# wearable.net
KiCad netlist of a schematic drawn in EAGLE
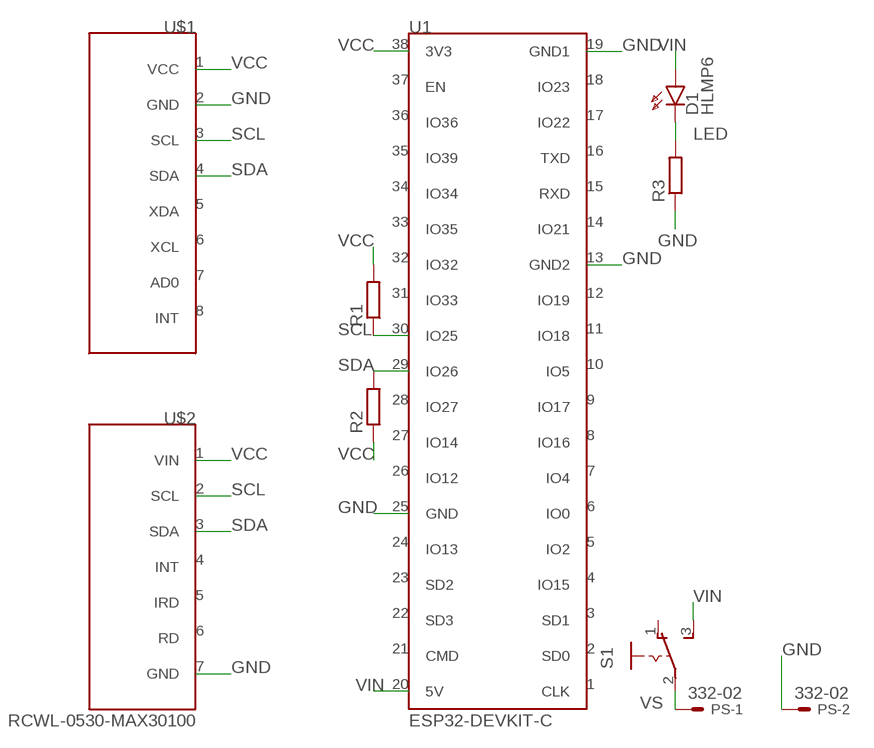
[diagram p0: schematic, sheet 1]

(export (version "E")
  (design (tool "Eeschema 10.0.6"))
  (components
    (comp (ref "D1")
      (value "HLMP6")
      (footprint "eagle-import:HLMP6")
      (fields (field (name "MF") "AGILENT TECHNOLOGIES") (field (name "MPN") "HLMP-6500"))
      (libsource (lib "eagle-import") (part "HLMP6"))
    )
    (comp (ref "PS")
      (value "332-02")
      (footprint "eagle-import:332-02")
      (libsource (lib "eagle-import") (part "332-02"))
    )
    (comp (ref "R1")
      (value "R-EU_0207/10")
      (footprint "eagle-import:0207_10")
      (libsource (lib "eagle-import") (part "R-EU_0207/10"))
    )
    (comp (ref "R2")
      (value "R-EU_0207/10")
      (footprint "eagle-import:0207_10")
      (libsource (lib "eagle-import") (part "R-EU_0207/10"))
    )
    (comp (ref "R3")
      (value "R-EU_0207/10")
      (footprint "eagle-import:0207_10")
      (libsource (lib "eagle-import") (part "R-EU_0207/10"))
    )
    (comp (ref "S1")
      (value "255SB")
      (footprint "eagle-import:255SB")
      (libsource (lib "eagle-import") (part "255SB"))
    )
    (comp (ref "U$1")
      (value "GY-521-MPU-6050")
      (footprint "eagle-import:GY-521")
      (libsource (lib "eagle-import") (part "GY-521-MPU-6050"))
    )
    (comp (ref "U$2")
      (value "RCWL-0530-MAX30100")
      (footprint "eagle-import:RCWL-0530")
      (libsource (lib "eagle-import") (part "RCWL-0530-MAX30100"))
    )
    (comp (ref "U1")
      (value "ESP32-DEVKIT-C")
      (footprint "eagle-import:ESP32")
      (libsource (lib "eagle-import") (part "ESP32-DEVKIT-C"))
    )
  )
  (nets
    (net (code "1") (name "/GND") (class "Default")
      (node (ref "PS") (pin "2") (pinfunction "S_2") (pintype "passive"))
      (node (ref "R3") (pin "1") (pinfunction "1_1") (pintype "passive"))
      (node (ref "U$1") (pin "2") (pinfunction "GND_2") (pintype "bidirectional"))
      (node (ref "U$2") (pin "7") (pinfunction "GND_7") (pintype "bidirectional"))
      (node (ref "U1") (pin "13") (pinfunction "GND2_13") (pintype "power_in"))
      (node (ref "U1") (pin "19") (pinfunction "GND1_19") (pintype "power_in"))
      (node (ref "U1") (pin "25") (pinfunction "GND_25") (pintype "power_in"))
    )
    (net (code "2") (name "/LED") (class "Default")
      (node (ref "D1") (pin "K") (pinfunction "K_K") (pintype "passive"))
      (node (ref "R3") (pin "2") (pinfunction "2_2") (pintype "passive"))
    )
    (net (code "3") (name "/SCL") (class "Default")
      (node (ref "R1") (pin "1") (pinfunction "1_1") (pintype "passive"))
      (node (ref "U$1") (pin "3") (pinfunction "SCL_3") (pintype "bidirectional"))
      (node (ref "U$2") (pin "2") (pinfunction "SCL_2") (pintype "bidirectional"))
      (node (ref "U1") (pin "30") (pinfunction "IO25_30") (pintype "bidirectional"))
    )
    (net (code "4") (name "/SDA") (class "Default")
      (node (ref "R2") (pin "2") (pinfunction "2_2") (pintype "passive"))
      (node (ref "U$1") (pin "4") (pinfunction "SDA_4") (pintype "bidirectional"))
      (node (ref "U$2") (pin "3") (pinfunction "SDA_3") (pintype "bidirectional"))
      (node (ref "U1") (pin "29") (pinfunction "IO26_29") (pintype "bidirectional"))
    )
    (net (code "5") (name "/VCC") (class "Default")
      (node (ref "R1") (pin "2") (pinfunction "2_2") (pintype "passive"))
      (node (ref "R2") (pin "1") (pinfunction "1_1") (pintype "passive"))
      (node (ref "U$1") (pin "1") (pinfunction "VCC_1") (pintype "bidirectional"))
      (node (ref "U$2") (pin "1") (pinfunction "VIN_1") (pintype "bidirectional"))
      (node (ref "U1") (pin "38") (pinfunction "3V3_38") (pintype "power_in"))
    )
    (net (code "6") (name "/VIN") (class "Default")
      (node (ref "D1") (pin "A") (pinfunction "A_A") (pintype "passive"))
      (node (ref "S1") (pin "3") (pinfunction "S_3") (pintype "passive"))
      (node (ref "U1") (pin "20") (pinfunction "5V_20") (pintype "power_in"))
    )
    (net (code "7") (name "/VS") (class "Default")
      (node (ref "PS") (pin "1") (pinfunction "S_1") (pintype "passive"))
      (node (ref "S1") (pin "2") (pinfunction "P_2") (pintype "passive"))
    )
    (net (code "8") (name "unconnected-(S1-O-Pad1)") (class "Default")
      (node (ref "S1") (pin "1") (pinfunction "O_1") (pintype "passive"))
    )
    (net (code "9") (name "unconnected-(U$1-AD0-Pad7)") (class "Default")
      (node (ref "U$1") (pin "7") (pinfunction "AD0_7") (pintype "bidirectional"))
    )
    (net (code "10") (name "unconnected-(U$1-INT-Pad8)") (class "Default")
      (node (ref "U$1") (pin "8") (pinfunction "INT_8") (pintype "bidirectional"))
    )
    (net (code "11") (name "unconnected-(U$1-XCL-Pad6)") (class "Default")
      (node (ref "U$1") (pin "6") (pinfunction "XCL_6") (pintype "bidirectional"))
    )
    (net (code "12") (name "unconnected-(U$1-XDA-Pad5)") (class "Default")
      (node (ref "U$1") (pin "5") (pinfunction "XDA_5") (pintype "bidirectional"))
    )
    (net (code "13") (name "unconnected-(U$2-INT-Pad4)") (class "Default")
      (node (ref "U$2") (pin "4") (pinfunction "INT_4") (pintype "bidirectional"))
    )
    (net (code "14") (name "unconnected-(U$2-IRD-Pad5)") (class "Default")
      (node (ref "U$2") (pin "5") (pinfunction "IRD_5") (pintype "bidirectional"))
    )
    (net (code "15") (name "unconnected-(U$2-RD-Pad6)") (class "Default")
      (node (ref "U$2") (pin "6") (pinfunction "RD_6") (pintype "bidirectional"))
    )
    (net (code "16") (name "unconnected-(U1-CLK-Pad1)") (class "Default")
      (node (ref "U1") (pin "1") (pinfunction "CLK_1") (pintype "no_connect"))
    )
    (net (code "17") (name "unconnected-(U1-CMD-Pad21)") (class "Default")
      (node (ref "U1") (pin "21") (pinfunction "CMD_21") (pintype "no_connect"))
    )
    (net (code "18") (name "unconnected-(U1-EN-Pad37)") (class "Default")
      (node (ref "U1") (pin "37") (pinfunction "EN_37") (pintype "bidirectional"))
    )
    (net (code "19") (name "unconnected-(U1-IO0-Pad6)") (class "Default")
      (node (ref "U1") (pin "6") (pinfunction "IO0_6") (pintype "output"))
    )
    (net (code "20") (name "unconnected-(U1-IO2-Pad5)") (class "Default")
      (node (ref "U1") (pin "5") (pinfunction "IO2_5") (pintype "output"))
    )
    (net (code "21") (name "unconnected-(U1-IO4-Pad7)") (class "Default")
      (node (ref "U1") (pin "7") (pinfunction "IO4_7") (pintype "output"))
    )
    (net (code "22") (name "unconnected-(U1-IO5-Pad10)") (class "Default")
      (node (ref "U1") (pin "10") (pinfunction "IO5_10") (pintype "output"))
    )
    (net (code "23") (name "unconnected-(U1-IO12-Pad26)") (class "Default")
      (node (ref "U1") (pin "26") (pinfunction "IO12_26") (pintype "output"))
    )
    (net (code "24") (name "unconnected-(U1-IO13-Pad24)") (class "Default")
      (node (ref "U1") (pin "24") (pinfunction "IO13_24") (pintype "bidirectional"))
    )
    (net (code "25") (name "unconnected-(U1-IO14-Pad27)") (class "Default")
      (node (ref "U1") (pin "27") (pinfunction "IO14_27") (pintype "bidirectional"))
    )
    (net (code "26") (name "unconnected-(U1-IO15-Pad4)") (class "Default")
      (node (ref "U1") (pin "4") (pinfunction "IO15_4") (pintype "output"))
    )
    (net (code "27") (name "unconnected-(U1-IO16-Pad8)") (class "Default")
      (node (ref "U1") (pin "8") (pinfunction "IO16_8") (pintype "bidirectional"))
    )
    (net (code "28") (name "unconnected-(U1-IO17-Pad9)") (class "Default")
      (node (ref "U1") (pin "9") (pinfunction "IO17_9") (pintype "bidirectional"))
    )
    (net (code "29") (name "unconnected-(U1-IO18-Pad11)") (class "Default")
      (node (ref "U1") (pin "11") (pinfunction "IO18_11") (pintype "bidirectional"))
    )
    (net (code "30") (name "unconnected-(U1-IO19-Pad12)") (class "Default")
      (node (ref "U1") (pin "12") (pinfunction "IO19_12") (pintype "bidirectional"))
    )
    (net (code "31") (name "unconnected-(U1-IO21-Pad14)") (class "Default")
      (node (ref "U1") (pin "14") (pinfunction "IO21_14") (pintype "bidirectional"))
    )
    (net (code "32") (name "unconnected-(U1-IO22-Pad17)") (class "Default")
      (node (ref "U1") (pin "17") (pinfunction "IO22_17") (pintype "bidirectional"))
    )
    (net (code "33") (name "unconnected-(U1-IO23-Pad18)") (class "Default")
      (node (ref "U1") (pin "18") (pinfunction "IO23_18") (pintype "bidirectional"))
    )
    (net (code "34") (name "unconnected-(U1-IO27-Pad28)") (class "Default")
      (node (ref "U1") (pin "28") (pinfunction "IO27_28") (pintype "bidirectional"))
    )
    (net (code "35") (name "unconnected-(U1-IO32-Pad32)") (class "Default")
      (node (ref "U1") (pin "32") (pinfunction "IO32_32") (pintype "bidirectional"))
    )
    (net (code "36") (name "unconnected-(U1-IO33-Pad31)") (class "Default")
      (node (ref "U1") (pin "31") (pinfunction "IO33_31") (pintype "bidirectional"))
    )
    (net (code "37") (name "unconnected-(U1-IO34-Pad34)") (class "Default")
      (node (ref "U1") (pin "34") (pinfunction "IO34_34") (pintype "input"))
    )
    (net (code "38") (name "unconnected-(U1-IO35-Pad33)") (class "Default")
      (node (ref "U1") (pin "33") (pinfunction "IO35_33") (pintype "input"))
    )
    (net (code "39") (name "unconnected-(U1-IO36-Pad36)") (class "Default")
      (node (ref "U1") (pin "36") (pinfunction "IO36_36") (pintype "input"))
    )
    (net (code "40") (name "unconnected-(U1-IO39-Pad35)") (class "Default")
      (node (ref "U1") (pin "35") (pinfunction "IO39_35") (pintype "input"))
    )
    (net (code "41") (name "unconnected-(U1-RXD-Pad15)") (class "Default")
      (node (ref "U1") (pin "15") (pinfunction "RXD_15") (pintype "no_connect"))
    )
    (net (code "42") (name "unconnected-(U1-SD0-Pad2)") (class "Default")
      (node (ref "U1") (pin "2") (pinfunction "SD0_2") (pintype "no_connect"))
    )
    (net (code "43") (name "unconnected-(U1-SD1-Pad3)") (class "Default")
      (node (ref "U1") (pin "3") (pinfunction "SD1_3") (pintype "no_connect"))
    )
    (net (code "44") (name "unconnected-(U1-SD2-Pad23)") (class "Default")
      (node (ref "U1") (pin "23") (pinfunction "SD2_23") (pintype "no_connect"))
    )
    (net (code "45") (name "unconnected-(U1-SD3-Pad22)") (class "Default")
      (node (ref "U1") (pin "22") (pinfunction "SD3_22") (pintype "no_connect"))
    )
    (net (code "46") (name "unconnected-(U1-TXD-Pad16)") (class "Default")
      (node (ref "U1") (pin "16") (pinfunction "TXD_16") (pintype "no_connect"))
    )
  )
)
